# MainFeeder_V1_0.net
KiCad netlist of a schematic drawn in EAGLE
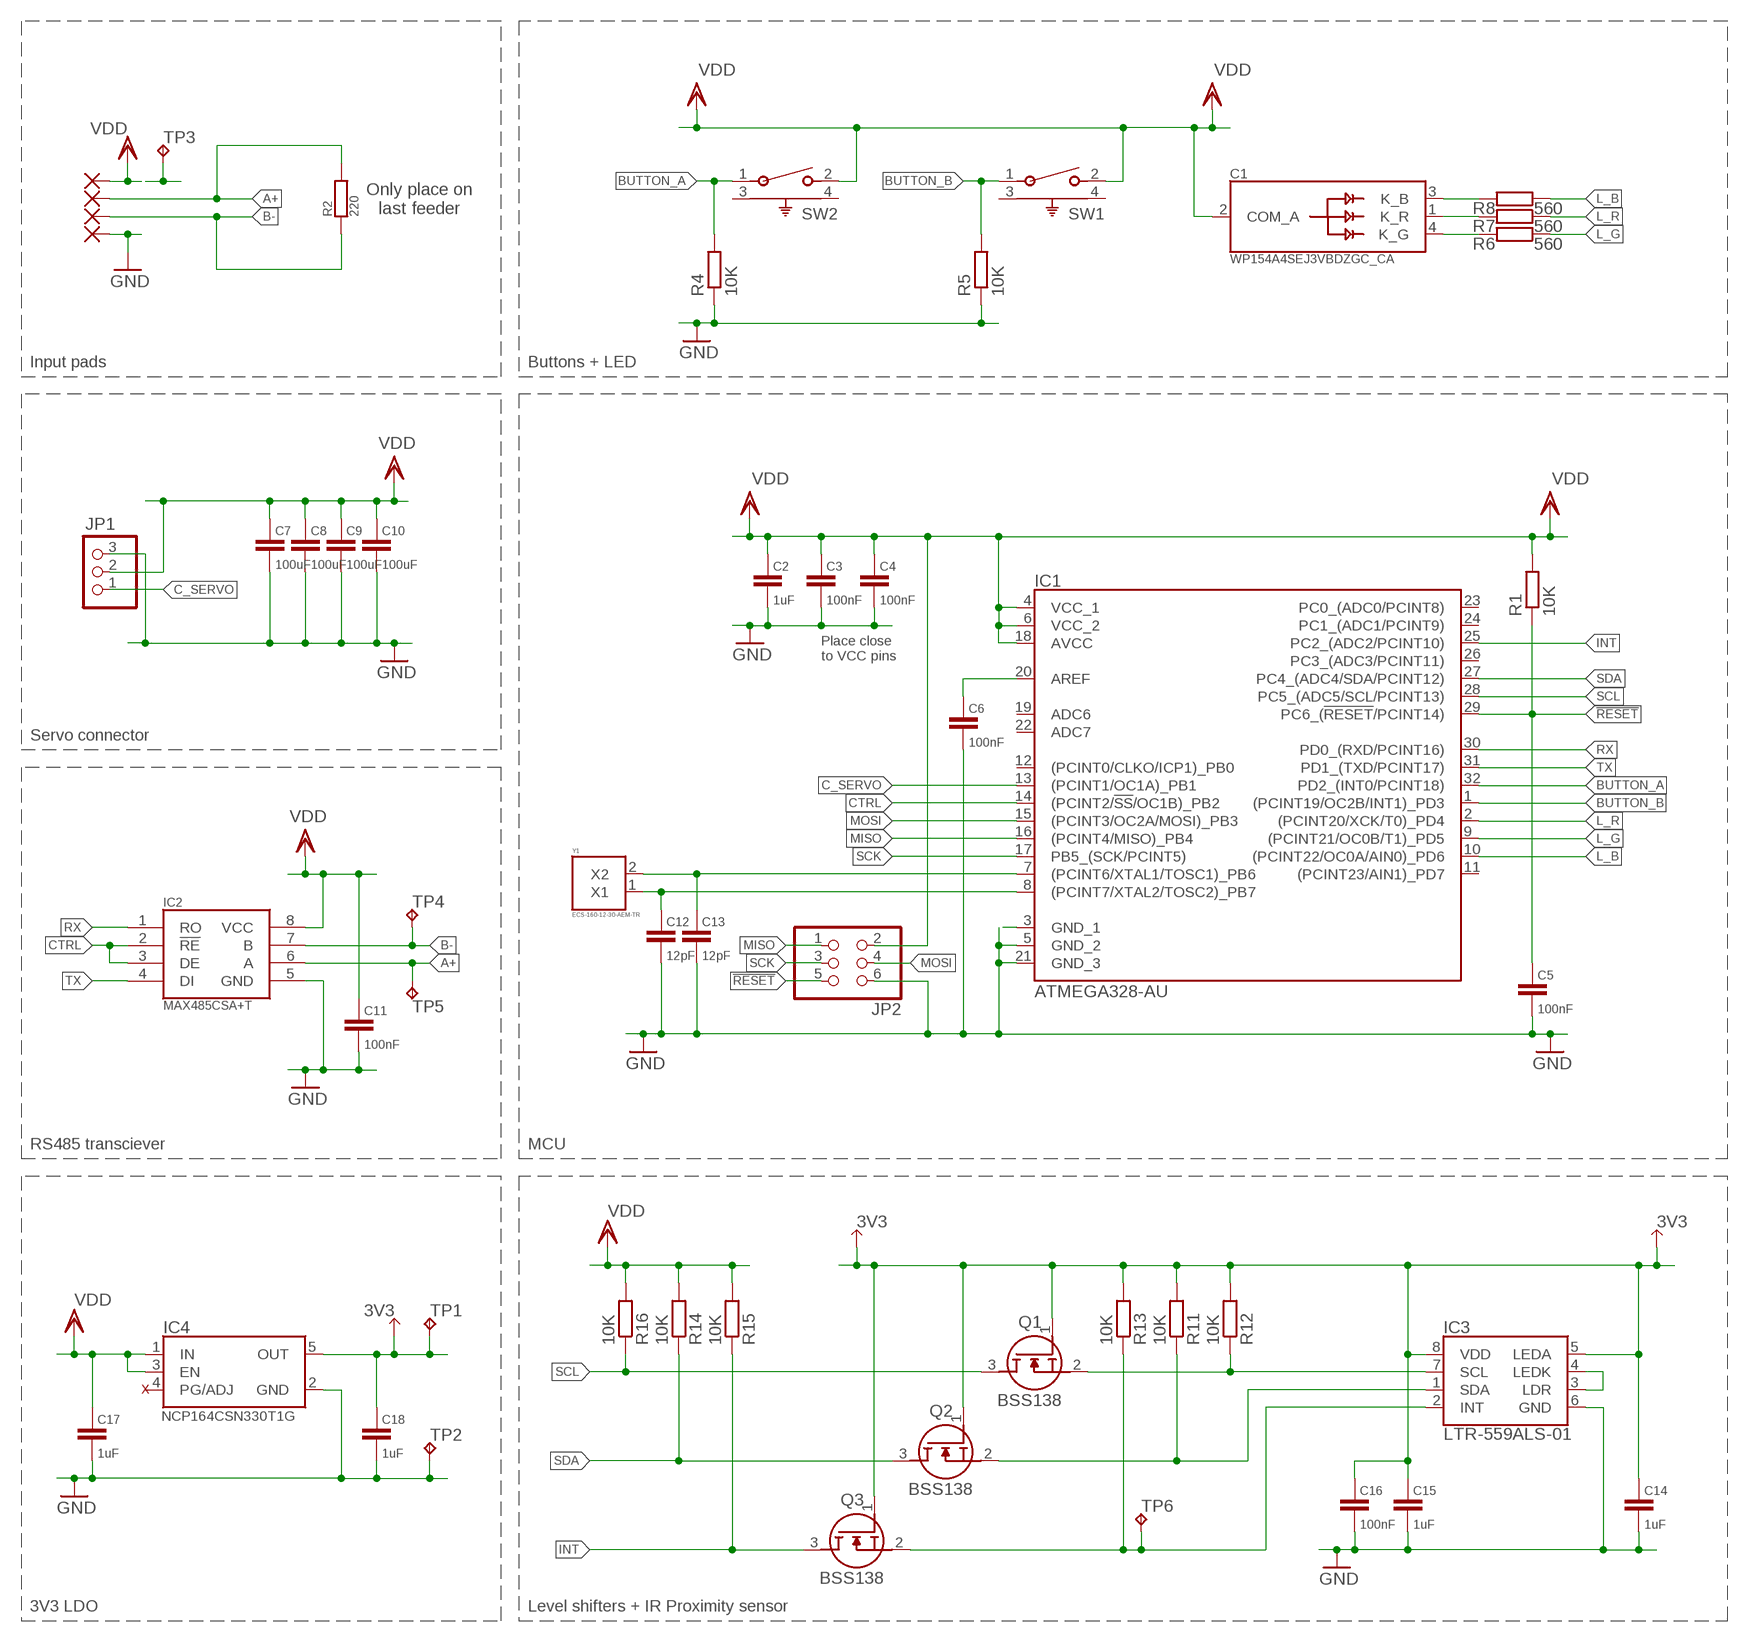
[diagram p0: schematic, sheet 1]

(export (version "E")
  (design (tool "Eeschema 10.0.6"))
  (components
    (comp (ref "C1")
      (value "WP154A4SEJ3VBDZGC_CA")
      (footprint "eagle-import:L-154A4SUREQBFZGEC")
      (fields
        (field (name "MANUFACTURER_PART_NUMBER") "WP154A4SEJ3VBDZGC/CA")
        (field (name "MOUSER_PART_NUMBER") "604-WP154A43VBDZGCCA")
      )
      (libsource (lib "eagle-import") (part "WP154A4SEJ3VBDZGC_CA"))
    )
    (comp (ref "C2")
      (value "1uF")
      (footprint "eagle-import:C0603")
      (libsource (lib "eagle-import") (part "C-EUC0603"))
    )
    (comp (ref "C3")
      (value "100nF")
      (footprint "eagle-import:C0603")
      (libsource (lib "eagle-import") (part "C-EUC0603"))
    )
    (comp (ref "C4")
      (value "100nF")
      (footprint "eagle-import:C0603")
      (libsource (lib "eagle-import") (part "C-EUC0603"))
    )
    (comp (ref "C5")
      (value "100nF")
      (footprint "eagle-import:C0603")
      (libsource (lib "eagle-import") (part "C-EUC0603"))
    )
    (comp (ref "C6")
      (value "100nF")
      (footprint "eagle-import:C0603")
      (libsource (lib "eagle-import") (part "C-EUC0603"))
    )
    (comp (ref "C7")
      (value "100uF")
      (footprint "eagle-import:C0805")
      (libsource (lib "eagle-import") (part "C-EUC0805"))
    )
    (comp (ref "C8")
      (value "100uF")
      (footprint "eagle-import:C0805")
      (libsource (lib "eagle-import") (part "C-EUC0805"))
    )
    (comp (ref "C9")
      (value "100uF")
      (footprint "eagle-import:C0805")
      (libsource (lib "eagle-import") (part "C-EUC0805"))
    )
    (comp (ref "C10")
      (value "100uF")
      (footprint "eagle-import:C0805")
      (libsource (lib "eagle-import") (part "C-EUC0805"))
    )
    (comp (ref "C11")
      (value "100nF")
      (footprint "eagle-import:C0603")
      (libsource (lib "eagle-import") (part "C-EUC0603"))
    )
    (comp (ref "C12")
      (value "12pF")
      (footprint "eagle-import:C0603")
      (libsource (lib "eagle-import") (part "C-EUC0603"))
    )
    (comp (ref "C13")
      (value "12pF")
      (footprint "eagle-import:C0603")
      (libsource (lib "eagle-import") (part "C-EUC0603"))
    )
    (comp (ref "C14")
      (value "1uF")
      (footprint "eagle-import:C0603")
      (libsource (lib "eagle-import") (part "C-EUC0603"))
    )
    (comp (ref "C15")
      (value "1uF")
      (footprint "eagle-import:C0603")
      (libsource (lib "eagle-import") (part "C-EUC0603"))
    )
    (comp (ref "C16")
      (value "100nF")
      (footprint "eagle-import:C0603")
      (libsource (lib "eagle-import") (part "C-EUC0603"))
    )
    (comp (ref "C17")
      (value "1uF")
      (footprint "eagle-import:C0603")
      (libsource (lib "eagle-import") (part "C-EUC0603"))
    )
    (comp (ref "C18")
      (value "1uF")
      (footprint "eagle-import:C0603")
      (libsource (lib "eagle-import") (part "C-EUC0603"))
    )
    (comp (ref "IC1")
      (value "ATMEGA328-AU")
      (footprint "eagle-import:QFP80P900X900X120-32N")
      (fields (field (name "MOUSER_PART_NUMBER") "556-ATMEGA328-AU"))
      (libsource (lib "eagle-import") (part "ATMEGA328-AU"))
    )
    (comp (ref "IC2")
      (value "MAX485CSA+T")
      (footprint "eagle-import:SOIC127P600X175-8N")
      (fields (field (name "MOUSER_PART_NUMBER") "700-MAX485CSAT"))
      (libsource (lib "eagle-import") (part "MAX485CSA+T"))
    )
    (comp (ref "IC3")
      (value "LTR-559ALS-01")
      (footprint "eagle-import:LTR559ALS01")
      (fields (field (name "MOUSER_PART_NUMBER") "859-LTR559ALS01"))
      (libsource (lib "eagle-import") (part "LTR-559ALS-01"))
    )
    (comp (ref "IC4")
      (value "NCP164CSN330T1G")
      (footprint "eagle-import:SOT95P275X110-5N")
      (fields (field (name "MOUSER_PART_NUMBER") "863-NCP164CSN330T1G"))
      (libsource (lib "eagle-import") (part "NCP164CSN330T1G"))
    )
    (comp (ref "JP1")
      (value "PINHD-1X3/90")
      (footprint "eagle-import:1X03_90")
      (libsource (lib "eagle-import") (part "PINHD-1X3/90"))
    )
    (comp (ref "JP2")
      (value "PINHD-2X3")
      (footprint "eagle-import:2X03")
      (libsource (lib "eagle-import") (part "PINHD-2X3"))
    )
    (comp (ref "PAD1")
      (value "SMD2")
      (footprint "eagle-import:SMD1,27-2,54")
      (libsource (lib "eagle-import") (part "SMD2"))
    )
    (comp (ref "PAD2")
      (value "SMD2")
      (footprint "eagle-import:SMD1,27-2,54")
      (libsource (lib "eagle-import") (part "SMD2"))
    )
    (comp (ref "PAD3")
      (value "SMD2")
      (footprint "eagle-import:SMD1,27-2,54")
      (libsource (lib "eagle-import") (part "SMD2"))
    )
    (comp (ref "PAD4")
      (value "SMD2")
      (footprint "eagle-import:SMD1,27-2,54")
      (libsource (lib "eagle-import") (part "SMD2"))
    )
    (comp (ref "Q1")
      (value "BSS138")
      (footprint "eagle-import:SOT95P240X120-3N")
      (fields (field (name "MOUSER_PART_NUMBER") "512-BSS138"))
      (libsource (lib "eagle-import") (part "BSS138"))
    )
    (comp (ref "Q2")
      (value "BSS138")
      (footprint "eagle-import:SOT95P240X120-3N")
      (fields (field (name "MOUSER_PART_NUMBER") "512-BSS138"))
      (libsource (lib "eagle-import") (part "BSS138"))
    )
    (comp (ref "Q3")
      (value "BSS138")
      (footprint "eagle-import:SOT95P240X120-3N")
      (fields (field (name "MOUSER_PART_NUMBER") "512-BSS138"))
      (libsource (lib "eagle-import") (part "BSS138"))
    )
    (comp (ref "R1")
      (value "10K")
      (footprint "eagle-import:R0603")
      (libsource (lib "eagle-import") (part "R-EU_R0603"))
    )
    (comp (ref "R2")
      (value "220")
      (footprint "eagle-import:R0603")
      (libsource (lib "eagle-import") (part "R-EU_R0603"))
    )
    (comp (ref "R4")
      (value "10K")
      (footprint "eagle-import:R0603")
      (libsource (lib "eagle-import") (part "R-EU_R0603"))
    )
    (comp (ref "R5")
      (value "10K")
      (footprint "eagle-import:R0603")
      (libsource (lib "eagle-import") (part "R-EU_R0603"))
    )
    (comp (ref "R6")
      (value "560")
      (footprint "eagle-import:R0603")
      (libsource (lib "eagle-import") (part "R-EU_R0603"))
    )
    (comp (ref "R7")
      (value "560")
      (footprint "eagle-import:R0603")
      (libsource (lib "eagle-import") (part "R-EU_R0603"))
    )
    (comp (ref "R8")
      (value "560")
      (footprint "eagle-import:R0603")
      (libsource (lib "eagle-import") (part "R-EU_R0603"))
    )
    (comp (ref "R11")
      (value "10K")
      (footprint "eagle-import:R0603")
      (libsource (lib "eagle-import") (part "R-EU_R0603"))
    )
    (comp (ref "R12")
      (value "10K")
      (footprint "eagle-import:R0603")
      (libsource (lib "eagle-import") (part "R-EU_R0603"))
    )
    (comp (ref "R13")
      (value "10K")
      (footprint "eagle-import:R0603")
      (libsource (lib "eagle-import") (part "R-EU_R0603"))
    )
    (comp (ref "R14")
      (value "10K")
      (footprint "eagle-import:R0603")
      (libsource (lib "eagle-import") (part "R-EU_R0603"))
    )
    (comp (ref "R15")
      (value "10K")
      (footprint "eagle-import:R0603")
      (libsource (lib "eagle-import") (part "R-EU_R0603"))
    )
    (comp (ref "R16")
      (value "10K")
      (footprint "eagle-import:R0603")
      (libsource (lib "eagle-import") (part "R-EU_R0603"))
    )
    (comp (ref "SW1")
      (value "1-1825027-1")
      (footprint "eagle-import:SW2_1825027-A_TEC")
      (fields (field (name "COPYRIGHT") "Copyright (C) 2016 Accelerated Designs. All rights reserved"))
      (libsource (lib "eagle-import") (part "1-1825027-1"))
    )
    (comp (ref "SW2")
      (value "1-1825027-1")
      (footprint "eagle-import:SW2_1825027-A_TEC")
      (fields (field (name "COPYRIGHT") "Copyright (C) 2016 Accelerated Designs. All rights reserved"))
      (libsource (lib "eagle-import") (part "1-1825027-1"))
    )
    (comp (ref "TP1")
      (value "TPB1,27")
      (footprint "eagle-import:B1,27")
      (libsource (lib "eagle-import") (part "TPB1,27"))
    )
    (comp (ref "TP2")
      (value "TPB1,27")
      (footprint "eagle-import:B1,27")
      (libsource (lib "eagle-import") (part "TPB1,27"))
    )
    (comp (ref "TP3")
      (value "TPB1,27")
      (footprint "eagle-import:B1,27")
      (libsource (lib "eagle-import") (part "TPB1,27"))
    )
    (comp (ref "TP4")
      (value "TPB1,27")
      (footprint "eagle-import:B1,27")
      (libsource (lib "eagle-import") (part "TPB1,27"))
    )
    (comp (ref "TP5")
      (value "TPB1,27")
      (footprint "eagle-import:B1,27")
      (libsource (lib "eagle-import") (part "TPB1,27"))
    )
    (comp (ref "TP6")
      (value "TPB1,27")
      (footprint "eagle-import:B1,27")
      (libsource (lib "eagle-import") (part "TPB1,27"))
    )
    (comp (ref "Y1")
      (value "ECS-160-12-30-AEM-TR")
      (footprint "eagle-import:ECS1601230AEMTR")
      (fields (field (name "MOUSER_PART_NUMBER") "520-160-12-30-AEM-TR"))
      (libsource (lib "eagle-import") (part "ECS-160-12-30-AEM-TR"))
    )
  )
  (nets
    (net (code "1") (name "/3V3") (class "Default")
      (node (ref "C14") (pin "1") (pinfunction "1_1") (pintype "passive"))
      (node (ref "C15") (pin "1") (pinfunction "1_1") (pintype "passive"))
      (node (ref "C16") (pin "1") (pinfunction "1_1") (pintype "passive"))
      (node (ref "C18") (pin "1") (pinfunction "1_1") (pintype "passive"))
      (node (ref "IC3") (pin "5") (pinfunction "LEDA_5") (pintype "bidirectional"))
      (node (ref "IC3") (pin "8") (pinfunction "VDD_8") (pintype "bidirectional"))
      (node (ref "IC4") (pin "5") (pinfunction "OUT_5") (pintype "bidirectional"))
      (node (ref "Q1") (pin "1") (pinfunction "G_1") (pintype "bidirectional"))
      (node (ref "Q2") (pin "1") (pinfunction "G_1") (pintype "bidirectional"))
      (node (ref "Q3") (pin "1") (pinfunction "G_1") (pintype "bidirectional"))
      (node (ref "R11") (pin "2") (pinfunction "2_2") (pintype "passive"))
      (node (ref "R12") (pin "2") (pinfunction "2_2") (pintype "passive"))
      (node (ref "R13") (pin "2") (pinfunction "2_2") (pintype "passive"))
      (node (ref "TP1") (pin "TP") (pinfunction "TP_TP") (pintype "input"))
    )
    (net (code "2") (name "/~{RESET}") (class "Default")
      (node (ref "C5") (pin "1") (pinfunction "1_1") (pintype "passive"))
      (node (ref "IC1") (pin "29") (pinfunction "PC6_(~{RESET}/PCINT14)_29") (pintype "input"))
      (node (ref "JP2") (pin "5") (pinfunction "5_5") (pintype "passive"))
      (node (ref "R1") (pin "1") (pinfunction "1_1") (pintype "passive"))
    )
    (net (code "3") (name "A+") (class "Default")
      (node (ref "IC2") (pin "6") (pinfunction "A_6") (pintype "bidirectional"))
      (node (ref "PAD1") (pin "1") (pinfunction "P_1") (pintype "passive"))
      (node (ref "R2") (pin "2") (pinfunction "2_2") (pintype "passive"))
      (node (ref "TP5") (pin "TP") (pinfunction "TP_TP") (pintype "input"))
    )
    (net (code "4") (name "B-") (class "Default")
      (node (ref "IC2") (pin "7") (pinfunction "B_7") (pintype "bidirectional"))
      (node (ref "PAD2") (pin "1") (pinfunction "P_1") (pintype "passive"))
      (node (ref "R2") (pin "1") (pinfunction "1_1") (pintype "passive"))
      (node (ref "TP4") (pin "TP") (pinfunction "TP_TP") (pintype "input"))
    )
    (net (code "5") (name "BUTTON_A") (class "Default")
      (node (ref "IC1") (pin "32") (pinfunction "PD2_(INT0/PCINT18)_32") (pintype "input"))
      (node (ref "R4") (pin "2") (pinfunction "2_2") (pintype "passive"))
      (node (ref "SW2") (pin "1") (pinfunction "1_1") (pintype "passive"))
    )
    (net (code "6") (name "BUTTON_B") (class "Default")
      (node (ref "IC1") (pin "1") (pinfunction "(PCINT19/OC2B/INT1)_PD3_1") (pintype "input"))
      (node (ref "R5") (pin "2") (pinfunction "2_2") (pintype "passive"))
      (node (ref "SW1") (pin "1") (pinfunction "1_1") (pintype "passive"))
    )
    (net (code "7") (name "CTRL") (class "Default")
      (node (ref "IC1") (pin "14") (pinfunction "(PCINT2/~{SS}/OC1B)_PB2_14") (pintype "input"))
      (node (ref "IC2") (pin "2") (pinfunction "~{RE}_2") (pintype "bidirectional"))
      (node (ref "IC2") (pin "3") (pinfunction "DE_3") (pintype "bidirectional"))
    )
    (net (code "8") (name "C_SERVO") (class "Default")
      (node (ref "IC1") (pin "13") (pinfunction "(PCINT1/OC1A)_PB1_13") (pintype "input"))
      (node (ref "JP1") (pin "1") (pinfunction "1_1") (pintype "passive"))
    )
    (net (code "9") (name "GND") (class "Default")
      (node (ref "C10") (pin "2") (pinfunction "2_2") (pintype "passive"))
      (node (ref "C11") (pin "2") (pinfunction "2_2") (pintype "passive"))
      (node (ref "C12") (pin "2") (pinfunction "2_2") (pintype "passive"))
      (node (ref "C13") (pin "2") (pinfunction "2_2") (pintype "passive"))
      (node (ref "C14") (pin "2") (pinfunction "2_2") (pintype "passive"))
      (node (ref "C15") (pin "2") (pinfunction "2_2") (pintype "passive"))
      (node (ref "C16") (pin "2") (pinfunction "2_2") (pintype "passive"))
      (node (ref "C17") (pin "2") (pinfunction "2_2") (pintype "passive"))
      (node (ref "C18") (pin "2") (pinfunction "2_2") (pintype "passive"))
      (node (ref "C2") (pin "2") (pinfunction "2_2") (pintype "passive"))
      (node (ref "C3") (pin "2") (pinfunction "2_2") (pintype "passive"))
      (node (ref "C4") (pin "2") (pinfunction "2_2") (pintype "passive"))
      (node (ref "C5") (pin "2") (pinfunction "2_2") (pintype "passive"))
      (node (ref "C6") (pin "2") (pinfunction "2_2") (pintype "passive"))
      (node (ref "C7") (pin "2") (pinfunction "2_2") (pintype "passive"))
      (node (ref "C8") (pin "2") (pinfunction "2_2") (pintype "passive"))
      (node (ref "C9") (pin "2") (pinfunction "2_2") (pintype "passive"))
      (node (ref "IC1") (pin "21") (pinfunction "GND_3_21") (pintype "power_in"))
      (node (ref "IC1") (pin "3") (pinfunction "GND_1_3") (pintype "power_in"))
      (node (ref "IC1") (pin "5") (pinfunction "GND_2_5") (pintype "power_in"))
      (node (ref "IC2") (pin "5") (pinfunction "GND_5") (pintype "bidirectional"))
      (node (ref "IC3") (pin "6") (pinfunction "GND_6") (pintype "bidirectional"))
      (node (ref "IC4") (pin "2") (pinfunction "GND_2") (pintype "bidirectional"))
      (node (ref "JP1") (pin "3") (pinfunction "3_3") (pintype "passive"))
      (node (ref "JP2") (pin "6") (pinfunction "6_6") (pintype "passive"))
      (node (ref "PAD3") (pin "1") (pinfunction "P_1") (pintype "passive"))
      (node (ref "R4") (pin "1") (pinfunction "1_1") (pintype "passive"))
      (node (ref "R5") (pin "1") (pinfunction "1_1") (pintype "passive"))
      (node (ref "TP2") (pin "TP") (pinfunction "TP_TP") (pintype "input"))
    )
    (net (code "10") (name "INT") (class "Default")
      (node (ref "IC1") (pin "25") (pinfunction "PC2_(ADC2/PCINT10)_25") (pintype "input"))
      (node (ref "Q3") (pin "3") (pinfunction "D_3") (pintype "bidirectional"))
      (node (ref "R15") (pin "1") (pinfunction "1_1") (pintype "passive"))
    )
    (net (code "11") (name "L_B") (class "Default")
      (node (ref "IC1") (pin "10") (pinfunction "(PCINT22/OC0A/AIN0)_PD6_10") (pintype "input"))
      (node (ref "R8") (pin "1") (pinfunction "1_1") (pintype "passive"))
    )
    (net (code "12") (name "L_G") (class "Default")
      (node (ref "IC1") (pin "9") (pinfunction "(PCINT21/OC0B/T1)_PD5_9") (pintype "input"))
      (node (ref "R6") (pin "1") (pinfunction "1_1") (pintype "passive"))
    )
    (net (code "13") (name "L_R") (class "Default")
      (node (ref "IC1") (pin "2") (pinfunction "(PCINT20/XCK/T0)_PD4_2") (pintype "input"))
      (node (ref "R7") (pin "1") (pinfunction "1_1") (pintype "passive"))
    )
    (net (code "14") (name "MISO") (class "Default")
      (node (ref "IC1") (pin "16") (pinfunction "(PCINT4/MISO)_PB4_16") (pintype "input"))
      (node (ref "JP2") (pin "1") (pinfunction "1_1") (pintype "passive"))
    )
    (net (code "15") (name "MOSI") (class "Default")
      (node (ref "IC1") (pin "15") (pinfunction "(PCINT3/OC2A/MOSI)_PB3_15") (pintype "input"))
      (node (ref "JP2") (pin "4") (pinfunction "4_4") (pintype "passive"))
    )
    (net (code "16") (name "Net-(C1-K_B)") (class "Default")
      (node (ref "C1") (pin "3") (pinfunction "K_B_3") (pintype "bidirectional"))
      (node (ref "R8") (pin "2") (pinfunction "2_2") (pintype "passive"))
    )
    (net (code "17") (name "Net-(C1-K_G)") (class "Default")
      (node (ref "C1") (pin "4") (pinfunction "K_G_4") (pintype "bidirectional"))
      (node (ref "R6") (pin "2") (pinfunction "2_2") (pintype "passive"))
    )
    (net (code "18") (name "Net-(C1-K_R)") (class "Default")
      (node (ref "C1") (pin "1") (pinfunction "K_R_1") (pintype "bidirectional"))
      (node (ref "R7") (pin "2") (pinfunction "2_2") (pintype "passive"))
    )
    (net (code "19") (name "Net-(IC1-(PCINT6{slash}XTAL1{slash}TOSC1)_PB6)") (class "Default")
      (node (ref "C13") (pin "1") (pinfunction "1_1") (pintype "passive"))
      (node (ref "IC1") (pin "7") (pinfunction "(PCINT6/XTAL1/TOSC1)_PB6_7") (pintype "input"))
      (node (ref "Y1") (pin "2") (pinfunction "X2_2") (pintype "bidirectional"))
    )
    (net (code "20") (name "Net-(IC1-(PCINT7{slash}XTAL2{slash}TOSC2)_PB7)") (class "Default")
      (node (ref "C12") (pin "1") (pinfunction "1_1") (pintype "passive"))
      (node (ref "IC1") (pin "8") (pinfunction "(PCINT7/XTAL2/TOSC2)_PB7_8") (pintype "input"))
      (node (ref "Y1") (pin "1") (pinfunction "X1_1") (pintype "bidirectional"))
    )
    (net (code "21") (name "Net-(IC1-AREF)") (class "Default")
      (node (ref "C6") (pin "1") (pinfunction "1_1") (pintype "passive"))
      (node (ref "IC1") (pin "20") (pinfunction "AREF_20") (pintype "input"))
    )
    (net (code "22") (name "Net-(IC3-INT)") (class "Default")
      (node (ref "IC3") (pin "2") (pinfunction "INT_2") (pintype "bidirectional"))
      (node (ref "Q3") (pin "2") (pinfunction "S_2") (pintype "bidirectional"))
      (node (ref "R13") (pin "1") (pinfunction "1_1") (pintype "passive"))
      (node (ref "TP6") (pin "TP") (pinfunction "TP_TP") (pintype "input"))
    )
    (net (code "23") (name "Net-(IC3-LDR)") (class "Default")
      (node (ref "IC3") (pin "3") (pinfunction "LDR_3") (pintype "bidirectional"))
      (node (ref "IC3") (pin "4") (pinfunction "LEDK_4") (pintype "bidirectional"))
    )
    (net (code "24") (name "Net-(IC3-SCL)") (class "Default")
      (node (ref "IC3") (pin "7") (pinfunction "SCL_7") (pintype "bidirectional"))
      (node (ref "Q1") (pin "2") (pinfunction "S_2") (pintype "bidirectional"))
      (node (ref "R12") (pin "1") (pinfunction "1_1") (pintype "passive"))
    )
    (net (code "25") (name "Net-(IC3-SDA)") (class "Default")
      (node (ref "IC3") (pin "1") (pinfunction "SDA_1") (pintype "bidirectional"))
      (node (ref "Q2") (pin "2") (pinfunction "S_2") (pintype "bidirectional"))
      (node (ref "R11") (pin "1") (pinfunction "1_1") (pintype "passive"))
    )
    (net (code "26") (name "RX") (class "Default")
      (node (ref "IC1") (pin "30") (pinfunction "PD0_(RXD/PCINT16)_30") (pintype "input"))
      (node (ref "IC2") (pin "1") (pinfunction "RO_1") (pintype "bidirectional"))
    )
    (net (code "27") (name "SCK") (class "Default")
      (node (ref "IC1") (pin "17") (pinfunction "PB5_(SCK/PCINT5)_17") (pintype "input"))
      (node (ref "JP2") (pin "3") (pinfunction "3_3") (pintype "passive"))
    )
    (net (code "28") (name "SCL") (class "Default")
      (node (ref "IC1") (pin "28") (pinfunction "PC5_(ADC5/SCL/PCINT13)_28") (pintype "input"))
      (node (ref "Q1") (pin "3") (pinfunction "D_3") (pintype "bidirectional"))
      (node (ref "R16") (pin "1") (pinfunction "1_1") (pintype "passive"))
    )
    (net (code "29") (name "SDA") (class "Default")
      (node (ref "IC1") (pin "27") (pinfunction "PC4_(ADC4/SDA/PCINT12)_27") (pintype "input"))
      (node (ref "Q2") (pin "3") (pinfunction "D_3") (pintype "bidirectional"))
      (node (ref "R14") (pin "1") (pinfunction "1_1") (pintype "passive"))
    )
    (net (code "30") (name "TX") (class "Default")
      (node (ref "IC1") (pin "31") (pinfunction "PD1_(TXD/PCINT17)_31") (pintype "input"))
      (node (ref "IC2") (pin "4") (pinfunction "DI_4") (pintype "bidirectional"))
    )
    (net (code "31") (name "VDD") (class "Default")
      (node (ref "C1") (pin "2") (pinfunction "COM_A_2") (pintype "bidirectional"))
      (node (ref "C10") (pin "1") (pinfunction "1_1") (pintype "passive"))
      (node (ref "C11") (pin "1") (pinfunction "1_1") (pintype "passive"))
      (node (ref "C17") (pin "1") (pinfunction "1_1") (pintype "passive"))
      (node (ref "C2") (pin "1") (pinfunction "1_1") (pintype "passive"))
      (node (ref "C3") (pin "1") (pinfunction "1_1") (pintype "passive"))
      (node (ref "C4") (pin "1") (pinfunction "1_1") (pintype "passive"))
      (node (ref "C7") (pin "1") (pinfunction "1_1") (pintype "passive"))
      (node (ref "C8") (pin "1") (pinfunction "1_1") (pintype "passive"))
      (node (ref "C9") (pin "1") (pinfunction "1_1") (pintype "passive"))
      (node (ref "IC1") (pin "18") (pinfunction "AVCC_18") (pintype "power_in"))
      (node (ref "IC1") (pin "4") (pinfunction "VCC_1_4") (pintype "power_in"))
      (node (ref "IC1") (pin "6") (pinfunction "VCC_2_6") (pintype "power_in"))
      (node (ref "IC2") (pin "8") (pinfunction "VCC_8") (pintype "bidirectional"))
      (node (ref "IC4") (pin "1") (pinfunction "IN_1") (pintype "bidirectional"))
      (node (ref "IC4") (pin "3") (pinfunction "EN_3") (pintype "bidirectional"))
      (node (ref "JP1") (pin "2") (pinfunction "2_2") (pintype "passive"))
      (node (ref "JP2") (pin "2") (pinfunction "2_2") (pintype "passive"))
      (node (ref "PAD4") (pin "1") (pinfunction "P_1") (pintype "passive"))
      (node (ref "R1") (pin "2") (pinfunction "2_2") (pintype "passive"))
      (node (ref "R14") (pin "2") (pinfunction "2_2") (pintype "passive"))
      (node (ref "R15") (pin "2") (pinfunction "2_2") (pintype "passive"))
      (node (ref "R16") (pin "2") (pinfunction "2_2") (pintype "passive"))
      (node (ref "SW1") (pin "2") (pinfunction "2_2") (pintype "passive"))
      (node (ref "SW2") (pin "2") (pinfunction "2_2") (pintype "passive"))
      (node (ref "TP3") (pin "TP") (pinfunction "TP_TP") (pintype "input"))
    )
    (net (code "32") (name "unconnected-(IC1-(PCINT0{slash}CLKO{slash}ICP1)_PB0-Pad12)") (class "Default")
      (node (ref "IC1") (pin "12") (pinfunction "(PCINT0/CLKO/ICP1)_PB0_12") (pintype "output"))
    )
    (net (code "33") (name "unconnected-(IC1-(PCINT23{slash}AIN1)_PD7-Pad11)") (class "Default")
      (node (ref "IC1") (pin "11") (pinfunction "(PCINT23/AIN1)_PD7_11") (pintype "input"))
    )
    (net (code "34") (name "unconnected-(IC1-ADC6-Pad19)") (class "Default")
      (node (ref "IC1") (pin "19") (pinfunction "ADC6_19") (pintype "bidirectional"))
    )
    (net (code "35") (name "unconnected-(IC1-ADC7-Pad22)") (class "Default")
      (node (ref "IC1") (pin "22") (pinfunction "ADC7_22") (pintype "bidirectional"))
    )
    (net (code "36") (name "unconnected-(IC1-PC0_(ADC0{slash}PCINT8)-Pad23)") (class "Default")
      (node (ref "IC1") (pin "23") (pinfunction "PC0_(ADC0/PCINT8)_23") (pintype "input"))
    )
    (net (code "37") (name "unconnected-(IC1-PC1_(ADC1{slash}PCINT9)-Pad24)") (class "Default")
      (node (ref "IC1") (pin "24") (pinfunction "PC1_(ADC1/PCINT9)_24") (pintype "input"))
    )
    (net (code "38") (name "unconnected-(IC1-PC3_(ADC3{slash}PCINT11)-Pad26)") (class "Default")
      (node (ref "IC1") (pin "26") (pinfunction "PC3_(ADC3/PCINT11)_26") (pintype "input"))
    )
    (net (code "39") (name "unconnected-(IC4-PG{slash}ADJ-Pad4)") (class "Default")
      (node (ref "IC4") (pin "4") (pinfunction "PG/ADJ_4") (pintype "bidirectional"))
    )
    (net (code "40") (name "unconnected-(SW1-Pad3)") (class "Default")
      (node (ref "SW1") (pin "3") (pinfunction "3_3") (pintype "passive"))
    )
    (net (code "41") (name "unconnected-(SW1-Pad4)") (class "Default")
      (node (ref "SW1") (pin "4") (pinfunction "4_4") (pintype "passive"))
    )
    (net (code "42") (name "unconnected-(SW2-Pad3)") (class "Default")
      (node (ref "SW2") (pin "3") (pinfunction "3_3") (pintype "passive"))
    )
    (net (code "43") (name "unconnected-(SW2-Pad4)") (class "Default")
      (node (ref "SW2") (pin "4") (pinfunction "4_4") (pintype "passive"))
    )
  )
)
